# SCH_SMD_VR_Conditioner_2023-05-26.net
KiCad netlist of a schematic drawn in EasyEDA
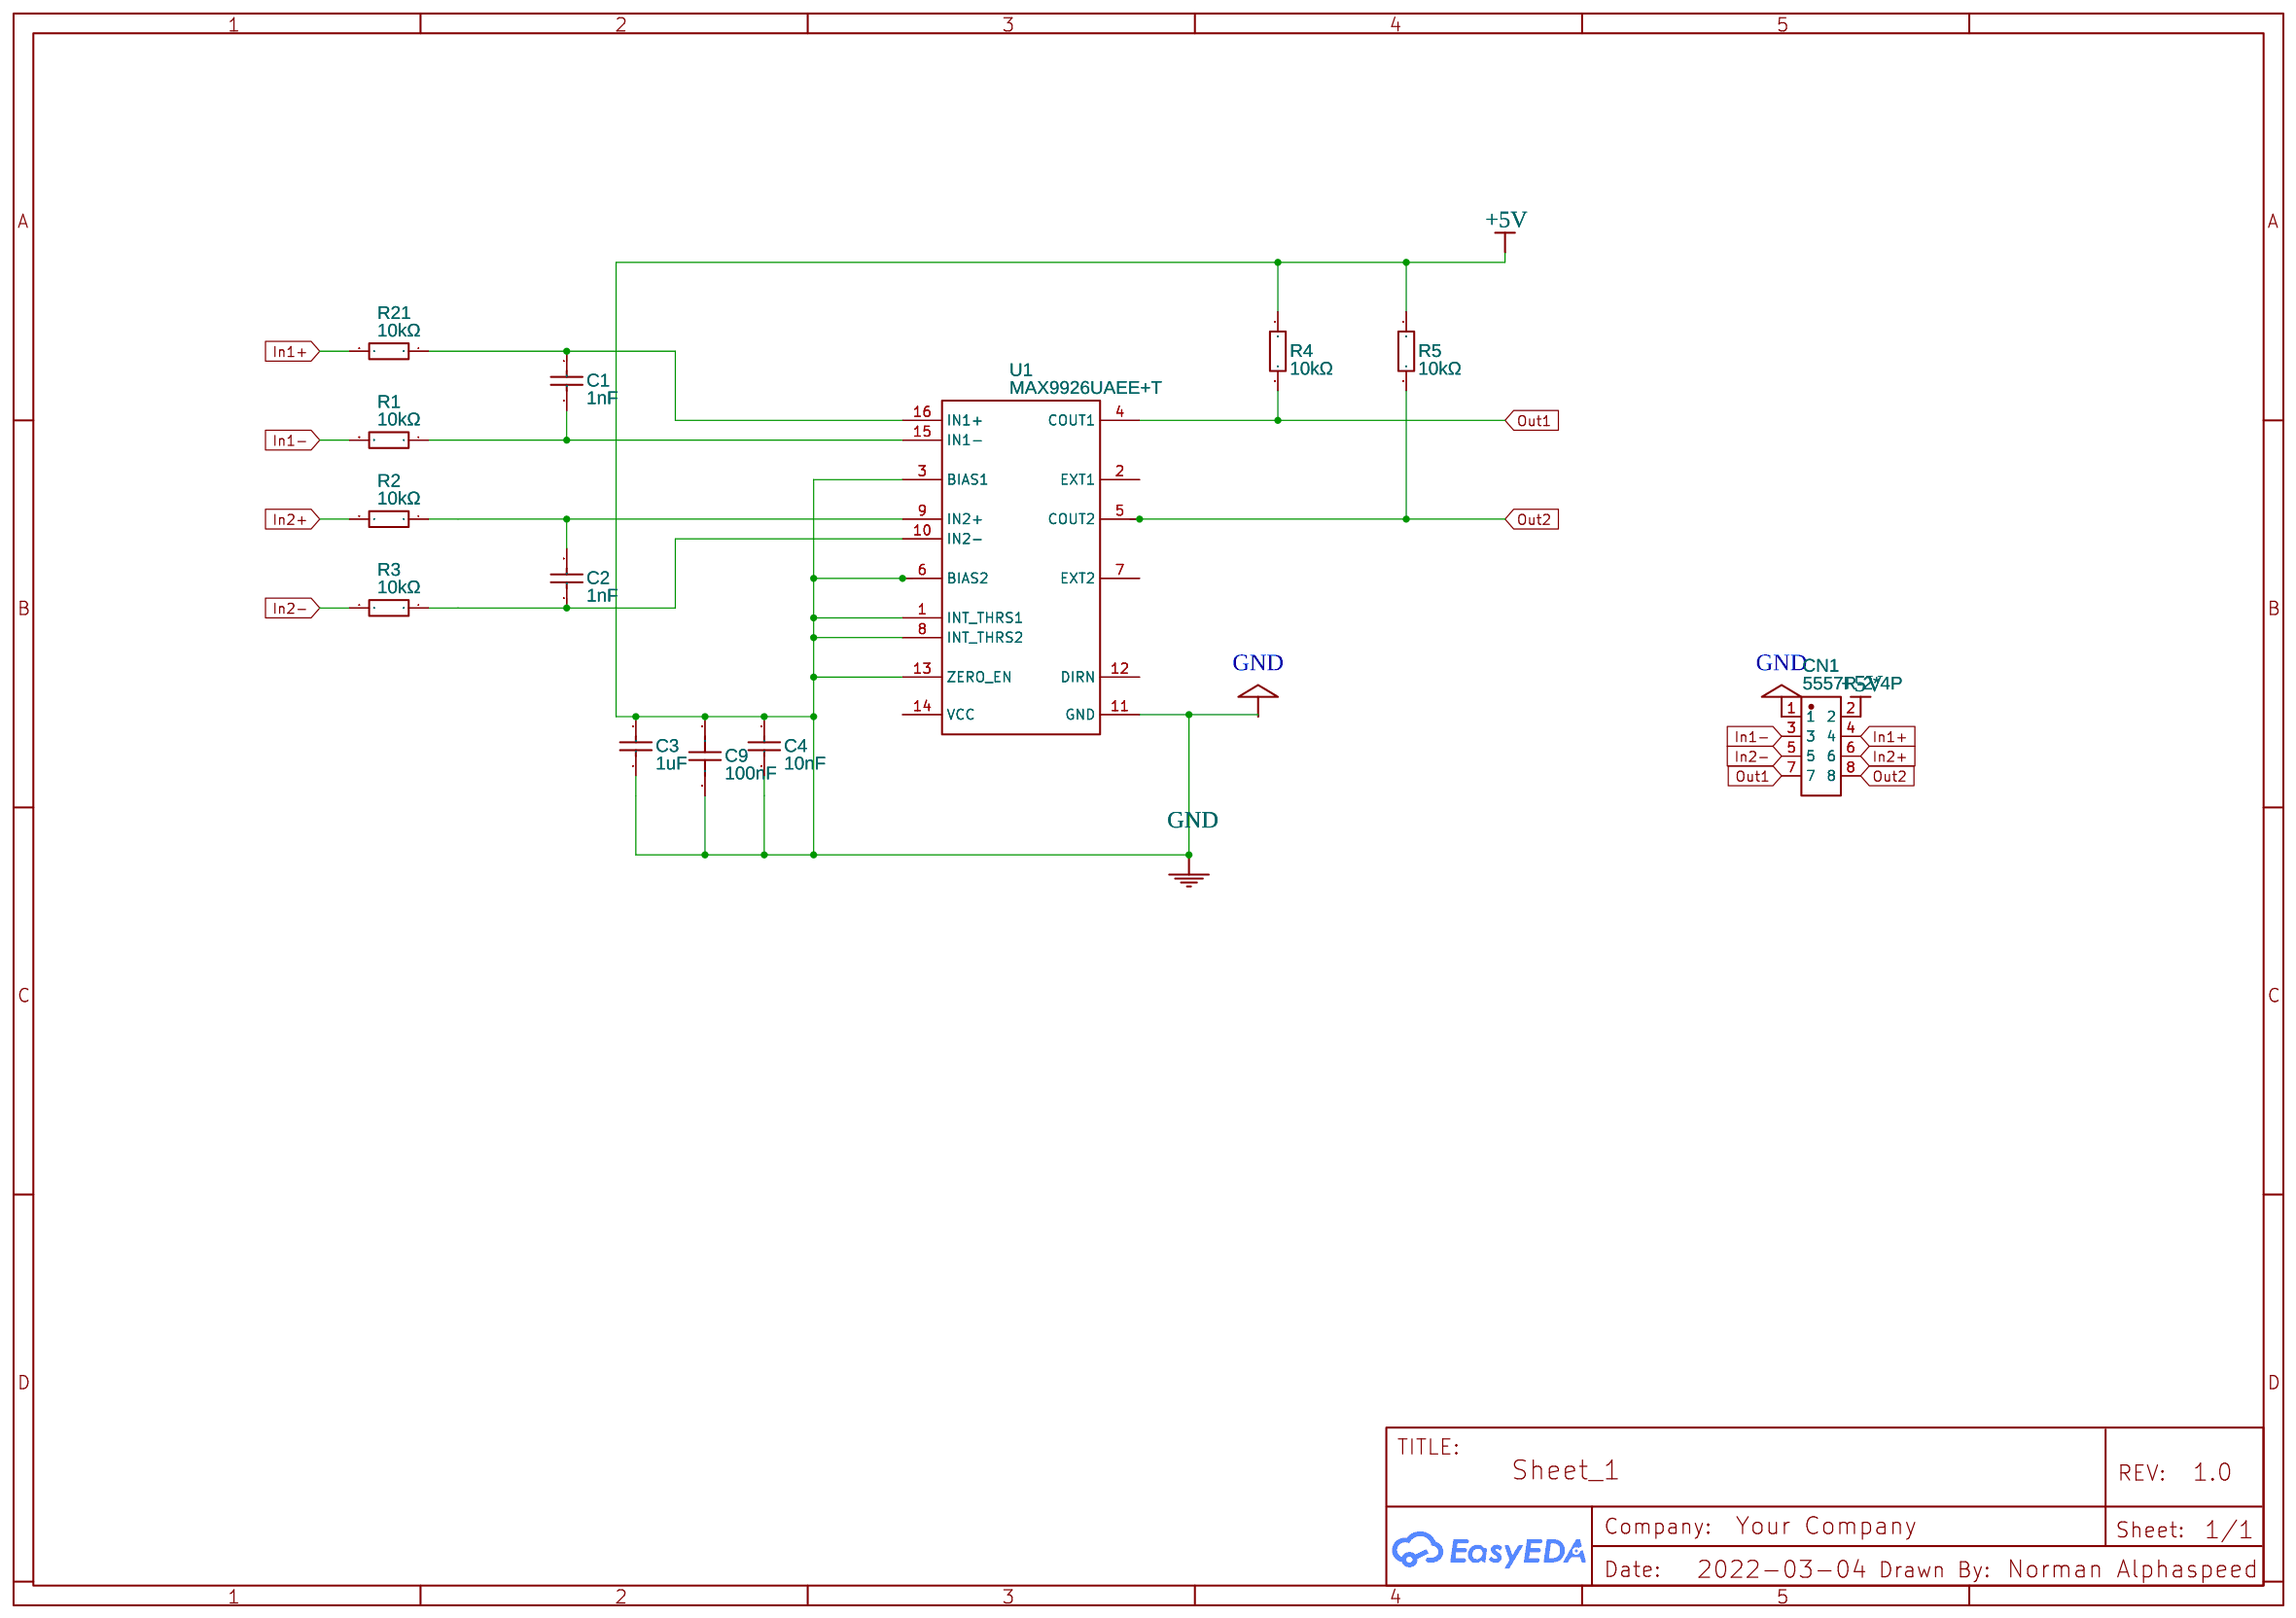
[diagram p0: schematic sheet]

(export (version "E")
  (design (tool "Eeschema 10.0.6"))
  (components
    (comp (ref "C1")
      (value "1nF")
      (fields
        (field (name "BOM_Manufacturer Part") "CL10B102KB8NNNC")
        (field (name "BOM_Supplier Part") "C1588")
      )
      (libsource (lib "") (part "CL10B102KB8NNNC"))
    )
    (comp (ref "C2")
      (value "1nF")
      (fields
        (field (name "BOM_Manufacturer Part") "CL10B102KB8NNNC")
        (field (name "BOM_Supplier Part") "C1588")
      )
      (libsource (lib "") (part "CL10B102KB8NNNC"))
    )
    (comp (ref "C3")
      (value "1uF")
      (fields
        (field (name "BOM_Manufacturer Part") "CL10A105KB8NNNC")
        (field (name "BOM_Supplier Part") "C15849")
      )
      (libsource (lib "") (part "CL10A105KB8NNNC"))
    )
    (comp (ref "C4")
      (value "10nF")
      (fields
        (field (name "BOM_Manufacturer Part") "CL05B103KB5NNNC")
        (field (name "BOM_Supplier Part") "C15195")
      )
      (libsource (lib "") (part "CL05B103KB5NNNC"))
    )
    (comp (ref "C9")
      (value "100nF")
      (fields
        (field (name "BOM_Manufacturer Part") "CC0603KRX7R9BB104")
        (field (name "BOM_Supplier Part") "C14663")
      )
      (libsource (lib "") (part "CC0603KRX7R9BB104"))
    )
    (comp (ref "CN1")
      (value "5557R-2*4P")
      (fields (field (name "BOM_Supplier Part") "C477838"))
      (libsource (lib "") (part "5557R-2*4P"))
    )
    (comp (ref "R1")
      (value "10kΩ")
      (fields
        (field (name "BOM_Manufacturer Part") "0402WGF1002TCE")
        (field (name "BOM_Supplier Part") "C25744")
      )
      (libsource (lib "") (part "0402WGF1002TCE"))
    )
    (comp (ref "R2")
      (value "10kΩ")
      (fields
        (field (name "BOM_Manufacturer Part") "0402WGF1002TCE")
        (field (name "BOM_Supplier Part") "C25744")
      )
      (libsource (lib "") (part "0402WGF1002TCE"))
    )
    (comp (ref "R3")
      (value "10kΩ")
      (fields
        (field (name "BOM_Manufacturer Part") "0402WGF1002TCE")
        (field (name "BOM_Supplier Part") "C25744")
      )
      (libsource (lib "") (part "0402WGF1002TCE"))
    )
    (comp (ref "R4")
      (value "10kΩ")
      (fields
        (field (name "BOM_Manufacturer Part") "0402WGF1002TCE")
        (field (name "BOM_Supplier Part") "C25744")
      )
      (libsource (lib "") (part "0402WGF1002TCE_1"))
    )
    (comp (ref "R5")
      (value "10kΩ")
      (fields
        (field (name "BOM_Manufacturer Part") "0402WGF1002TCE")
        (field (name "BOM_Supplier Part") "C25744")
      )
      (libsource (lib "") (part "0402WGF1002TCE_1"))
    )
    (comp (ref "R21")
      (value "10kΩ")
      (fields
        (field (name "BOM_Manufacturer Part") "0402WGF1002TCE")
        (field (name "BOM_Supplier Part") "C25744")
      )
      (libsource (lib "") (part "0402WGF1002TCE"))
    )
    (comp (ref "U1")
      (value "MAX9926UAEE+T")
      (fields (field (name "BOM_Manufacturer Part") "?"))
      (libsource (lib "") (part "Unknown_510_-520"))
    )
  )
  (nets
    (net (code "1") (name "+5V") (class "Default")
      (node (ref "C3") (pin "1") (pinfunction "1_1") (pintype "input"))
      (node (ref "C3") (pin "2") (pinfunction "2_2") (pintype "input"))
      (node (ref "C4") (pin "1") (pinfunction "1_1") (pintype "input"))
      (node (ref "C4") (pin "2") (pinfunction "2_2") (pintype "input"))
      (node (ref "C9") (pin "1") (pinfunction "1_1") (pintype "unspecified"))
      (node (ref "C9") (pin "2") (pinfunction "2_2") (pintype "unspecified"))
      (node (ref "CN1") (pin "1") (pinfunction "1_1") (pintype "unspecified"))
      (node (ref "CN1") (pin "2") (pinfunction "2_2") (pintype "unspecified"))
      (node (ref "R4") (pin "1") (pinfunction "1_1") (pintype "input"))
      (node (ref "R5") (pin "1") (pinfunction "1_1") (pintype "input"))
      (node (ref "U1") (pin "1") (pinfunction "INT_THRS1_1") (pintype "unspecified"))
      (node (ref "U1") (pin "11") (pinfunction "GND_11") (pintype "passive"))
      (node (ref "U1") (pin "13") (pinfunction "ZERO_EN_13") (pintype "unspecified"))
      (node (ref "U1") (pin "3") (pinfunction "BIAS1_3") (pintype "unspecified"))
      (node (ref "U1") (pin "6") (pinfunction "BIAS2_6") (pintype "unspecified"))
      (node (ref "U1") (pin "8") (pinfunction "INT_THRS2_8") (pintype "unspecified"))
    )
    (net (code "2") (name "In1+") (class "Default")
      (node (ref "CN1") (pin "4") (pinfunction "4_4") (pintype "unspecified"))
      (node (ref "R21") (pin "2") (pinfunction "2_2") (pintype "input"))
    )
    (net (code "3") (name "In1-") (class "Default")
      (node (ref "CN1") (pin "3") (pinfunction "3_3") (pintype "unspecified"))
      (node (ref "R1") (pin "2") (pinfunction "2_2") (pintype "input"))
    )
    (net (code "4") (name "In2+") (class "Default")
      (node (ref "CN1") (pin "6") (pinfunction "6_6") (pintype "unspecified"))
      (node (ref "R2") (pin "2") (pinfunction "2_2") (pintype "input"))
    )
    (net (code "5") (name "In2-") (class "Default")
      (node (ref "CN1") (pin "5") (pinfunction "5_5") (pintype "unspecified"))
      (node (ref "R3") (pin "2") (pinfunction "2_2") (pintype "input"))
    )
    (net (code "6") (name "Net-(U1-IN1+)") (class "Default")
      (node (ref "C1") (pin "2") (pinfunction "2_2") (pintype "input"))
      (node (ref "R21") (pin "1") (pinfunction "1_1") (pintype "input"))
      (node (ref "U1") (pin "16") (pinfunction "IN1+_16") (pintype "unspecified"))
    )
    (net (code "7") (name "Net-(U1-IN1-)") (class "Default")
      (node (ref "C1") (pin "1") (pinfunction "1_1") (pintype "input"))
      (node (ref "R1") (pin "1") (pinfunction "1_1") (pintype "input"))
      (node (ref "U1") (pin "15") (pinfunction "IN1-_15") (pintype "unspecified"))
    )
    (net (code "8") (name "Net-(U1-IN2+)") (class "Default")
      (node (ref "C2") (pin "2") (pinfunction "2_2") (pintype "input"))
      (node (ref "R2") (pin "1") (pinfunction "1_1") (pintype "input"))
      (node (ref "U1") (pin "9") (pinfunction "IN2+_9") (pintype "unspecified"))
    )
    (net (code "9") (name "Net-(U1-IN2-)") (class "Default")
      (node (ref "C2") (pin "1") (pinfunction "1_1") (pintype "input"))
      (node (ref "R3") (pin "1") (pinfunction "1_1") (pintype "input"))
      (node (ref "U1") (pin "10") (pinfunction "IN2-_10") (pintype "unspecified"))
    )
    (net (code "10") (name "Out1") (class "Default")
      (node (ref "CN1") (pin "7") (pinfunction "7_7") (pintype "unspecified"))
      (node (ref "R4") (pin "2") (pinfunction "2_2") (pintype "input"))
      (node (ref "U1") (pin "4") (pinfunction "COUT1_4") (pintype "unspecified"))
    )
    (net (code "11") (name "Out2") (class "Default")
      (node (ref "CN1") (pin "8") (pinfunction "8_8") (pintype "unspecified"))
      (node (ref "R5") (pin "2") (pinfunction "2_2") (pintype "input"))
      (node (ref "U1") (pin "5") (pinfunction "COUT2_5") (pintype "unspecified"))
    )
    (net (code "12") (name "unconnected-(U1-DIRN-Pad12)") (class "Default")
      (node (ref "U1") (pin "12") (pinfunction "DIRN_12") (pintype "unspecified"))
    )
    (net (code "13") (name "unconnected-(U1-EXT1-Pad2)") (class "Default")
      (node (ref "U1") (pin "2") (pinfunction "EXT1_2") (pintype "unspecified"))
    )
    (net (code "14") (name "unconnected-(U1-EXT2-Pad7)") (class "Default")
      (node (ref "U1") (pin "7") (pinfunction "EXT2_7") (pintype "unspecified"))
    )
    (net (code "15") (name "unconnected-(U1-VCC-Pad14)") (class "Default")
      (node (ref "U1") (pin "14") (pinfunction "VCC_14") (pintype "passive"))
    )
  )
)
